# LOA_Damballah.net
KiCad netlist of a schematic drawn in EAGLE
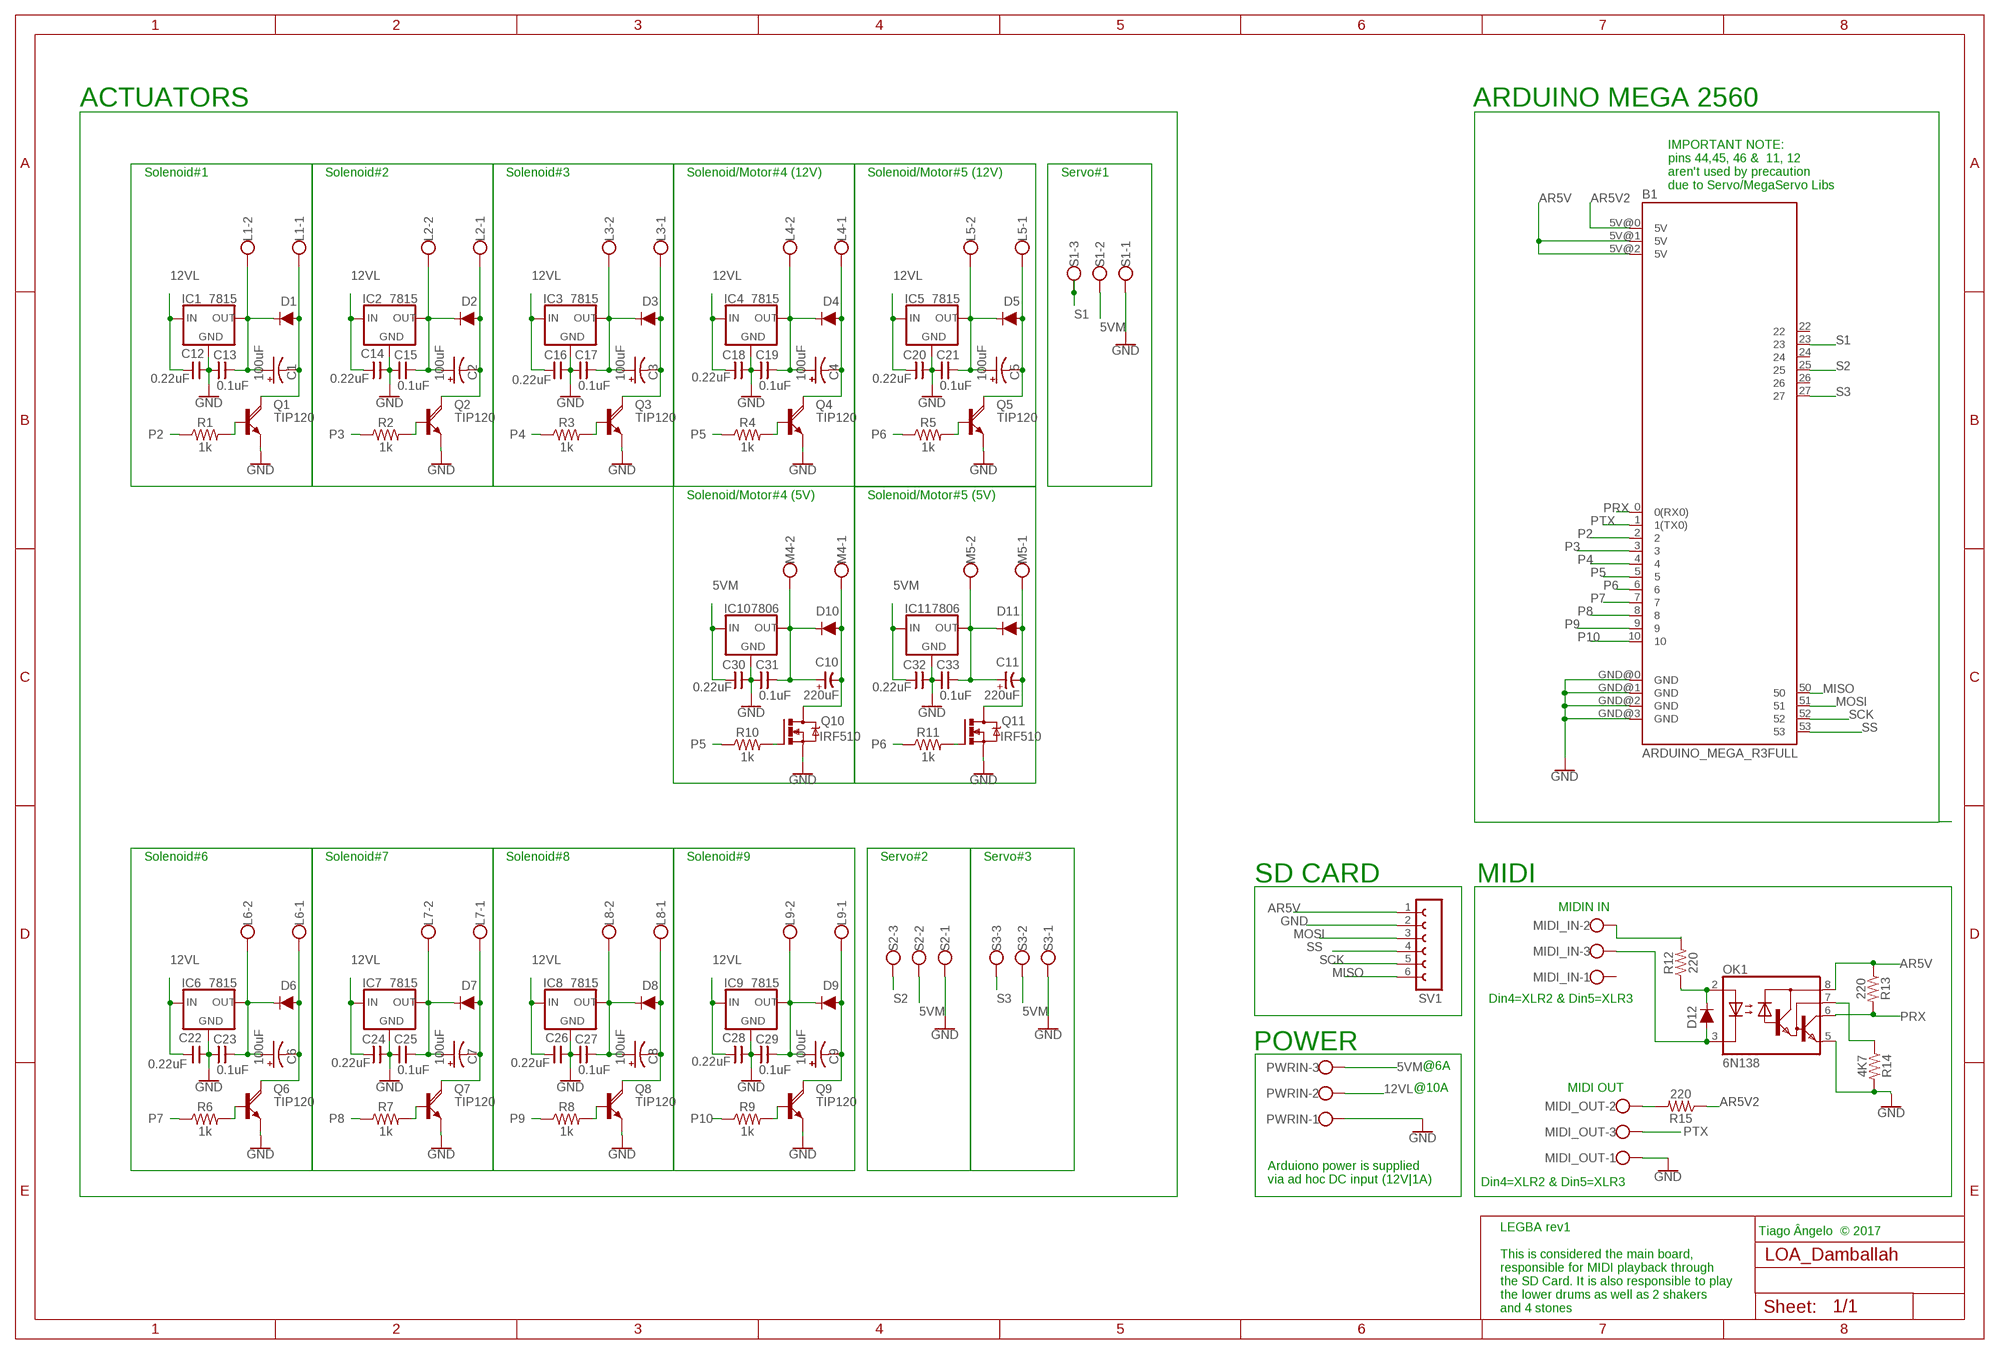
[diagram p0: schematic, sheet 1]

(export (version "E")
  (design (tool "Eeschema 10.0.6"))
  (components
    (comp (ref "B1")
      (value "ARDUINO_MEGA_R3FULL")
      (footprint "eagle-import:ARDUINO_MEGA")
      (libsource (lib "eagle-import") (part "ARDUINO_MEGA_R3FULL"))
    )
    (comp (ref "C1")
      (value "100uF")
      (footprint "eagle-import:E3,5-8")
      (libsource (lib "eagle-import") (part "CPOL-USE3.5-8"))
    )
    (comp (ref "C2")
      (value "100uF")
      (footprint "eagle-import:E3,5-8")
      (libsource (lib "eagle-import") (part "CPOL-USE3.5-8"))
    )
    (comp (ref "C3")
      (value "100uF")
      (footprint "eagle-import:E3,5-8")
      (libsource (lib "eagle-import") (part "CPOL-USE3.5-8"))
    )
    (comp (ref "C4")
      (value "100uF")
      (footprint "eagle-import:E3,5-8")
      (libsource (lib "eagle-import") (part "CPOL-USE3.5-8"))
    )
    (comp (ref "C5")
      (value "100uF")
      (footprint "eagle-import:E3,5-8")
      (libsource (lib "eagle-import") (part "CPOL-USE3.5-8"))
    )
    (comp (ref "C6")
      (value "100uF")
      (footprint "eagle-import:E3,5-8")
      (libsource (lib "eagle-import") (part "CPOL-USE3.5-8"))
    )
    (comp (ref "C7")
      (value "100uF")
      (footprint "eagle-import:E3,5-8")
      (libsource (lib "eagle-import") (part "CPOL-USE3.5-8"))
    )
    (comp (ref "C8")
      (value "100uF")
      (footprint "eagle-import:E3,5-8")
      (libsource (lib "eagle-import") (part "CPOL-USE3.5-8"))
    )
    (comp (ref "C9")
      (value "100uF")
      (footprint "eagle-import:E3,5-8")
      (libsource (lib "eagle-import") (part "CPOL-USE3.5-8"))
    )
    (comp (ref "C10")
      (value "220uF")
      (footprint "eagle-import:E-035X080")
      (libsource (lib "eagle-import") (part "CP-E-035X080"))
    )
    (comp (ref "C11")
      (value "220uF")
      (footprint "eagle-import:E-035X080")
      (libsource (lib "eagle-import") (part "CP-E-035X080"))
    )
    (comp (ref "C12")
      (value "0.22uF")
      (footprint "eagle-import:C025-050X025")
      (libsource (lib "eagle-import") (part "CNP-C025-050X025"))
    )
    (comp (ref "C13")
      (value "0.1uF")
      (footprint "eagle-import:C025-050X025")
      (libsource (lib "eagle-import") (part "CNP-C025-050X025"))
    )
    (comp (ref "C14")
      (value "0.22uF")
      (footprint "eagle-import:C025-050X025")
      (libsource (lib "eagle-import") (part "CNP-C025-050X025"))
    )
    (comp (ref "C15")
      (value "0.1uF")
      (footprint "eagle-import:C025-050X025")
      (libsource (lib "eagle-import") (part "CNP-C025-050X025"))
    )
    (comp (ref "C16")
      (value "0.22uF")
      (footprint "eagle-import:C025-050X025")
      (libsource (lib "eagle-import") (part "CNP-C025-050X025"))
    )
    (comp (ref "C17")
      (value "0.1uF")
      (footprint "eagle-import:C025-050X025")
      (libsource (lib "eagle-import") (part "CNP-C025-050X025"))
    )
    (comp (ref "C18")
      (value "0.22uF")
      (footprint "eagle-import:C025-050X025")
      (libsource (lib "eagle-import") (part "CNP-C025-050X025"))
    )
    (comp (ref "C19")
      (value "0.1uF")
      (footprint "eagle-import:C025-050X025")
      (libsource (lib "eagle-import") (part "CNP-C025-050X025"))
    )
    (comp (ref "C20")
      (value "0.22uF")
      (footprint "eagle-import:C025-050X025")
      (libsource (lib "eagle-import") (part "CNP-C025-050X025"))
    )
    (comp (ref "C21")
      (value "0.1uF")
      (footprint "eagle-import:C025-050X025")
      (libsource (lib "eagle-import") (part "CNP-C025-050X025"))
    )
    (comp (ref "C22")
      (value "0.22uF")
      (footprint "eagle-import:C025-050X025")
      (libsource (lib "eagle-import") (part "CNP-C025-050X025"))
    )
    (comp (ref "C23")
      (value "0.1uF")
      (footprint "eagle-import:C025-050X025")
      (libsource (lib "eagle-import") (part "CNP-C025-050X025"))
    )
    (comp (ref "C24")
      (value "0.22uF")
      (footprint "eagle-import:C025-050X025")
      (libsource (lib "eagle-import") (part "CNP-C025-050X025"))
    )
    (comp (ref "C25")
      (value "0.1uF")
      (footprint "eagle-import:C025-050X025")
      (libsource (lib "eagle-import") (part "CNP-C025-050X025"))
    )
    (comp (ref "C26")
      (value "0.22uF")
      (footprint "eagle-import:C025-050X025")
      (libsource (lib "eagle-import") (part "CNP-C025-050X025"))
    )
    (comp (ref "C27")
      (value "0.1uF")
      (footprint "eagle-import:C025-050X025")
      (libsource (lib "eagle-import") (part "CNP-C025-050X025"))
    )
    (comp (ref "C28")
      (value "0.22uF")
      (footprint "eagle-import:C025-050X025")
      (libsource (lib "eagle-import") (part "CNP-C025-050X025"))
    )
    (comp (ref "C29")
      (value "0.1uF")
      (footprint "eagle-import:C025-050X025")
      (libsource (lib "eagle-import") (part "CNP-C025-050X025"))
    )
    (comp (ref "C30")
      (value "0.22uF")
      (footprint "eagle-import:C025-050X025")
      (libsource (lib "eagle-import") (part "CNP-C025-050X025"))
    )
    (comp (ref "C31")
      (value "0.1uF")
      (footprint "eagle-import:C025-050X025")
      (libsource (lib "eagle-import") (part "CNP-C025-050X025"))
    )
    (comp (ref "C32")
      (value "0.22uF")
      (footprint "eagle-import:C025-050X025")
      (libsource (lib "eagle-import") (part "CNP-C025-050X025"))
    )
    (comp (ref "C33")
      (value "0.1uF")
      (footprint "eagle-import:C025-050X025")
      (libsource (lib "eagle-import") (part "CNP-C025-050X025"))
    )
    (comp (ref "D1")
      (value "1A/50V/1.1V")
      (footprint "eagle-import:DIODE-1N4001-KIT")
      (libsource (lib "eagle-import") (part "DIODE-KIT2"))
    )
    (comp (ref "D2")
      (value "1A/50V/1.1V")
      (footprint "eagle-import:DIODE-1N4001-KIT")
      (libsource (lib "eagle-import") (part "DIODE-KIT2"))
    )
    (comp (ref "D3")
      (value "1A/50V/1.1V")
      (footprint "eagle-import:DIODE-1N4001-KIT")
      (libsource (lib "eagle-import") (part "DIODE-KIT2"))
    )
    (comp (ref "D4")
      (value "1A/50V/1.1V")
      (footprint "eagle-import:DIODE-1N4001-KIT")
      (libsource (lib "eagle-import") (part "DIODE-KIT2"))
    )
    (comp (ref "D5")
      (value "1A/50V/1.1V")
      (footprint "eagle-import:DIODE-1N4001-KIT")
      (libsource (lib "eagle-import") (part "DIODE-KIT2"))
    )
    (comp (ref "D6")
      (value "1A/50V/1.1V")
      (footprint "eagle-import:DIODE-1N4001-KIT")
      (libsource (lib "eagle-import") (part "DIODE-KIT2"))
    )
    (comp (ref "D7")
      (value "1A/50V/1.1V")
      (footprint "eagle-import:DIODE-1N4001-KIT")
      (libsource (lib "eagle-import") (part "DIODE-KIT2"))
    )
    (comp (ref "D8")
      (value "1A/50V/1.1V")
      (footprint "eagle-import:DIODE-1N4001-KIT")
      (libsource (lib "eagle-import") (part "DIODE-KIT2"))
    )
    (comp (ref "D9")
      (value "1A/50V/1.1V")
      (footprint "eagle-import:DIODE-1N4001-KIT")
      (libsource (lib "eagle-import") (part "DIODE-KIT2"))
    )
    (comp (ref "D10")
      (value "1A/50V/1.1V")
      (footprint "eagle-import:DIODE-1N4001-KIT")
      (libsource (lib "eagle-import") (part "DIODE-KIT2"))
    )
    (comp (ref "D11")
      (value "1A/50V/1.1V")
      (footprint "eagle-import:DIODE-1N4001-KIT")
      (libsource (lib "eagle-import") (part "DIODE-KIT2"))
    )
    (comp (ref "D12")
      (value "200mA/100V/1V")
      (footprint "eagle-import:DIODE-1N4148")
      (libsource (lib "eagle-import") (part "DIODE-1N4148"))
    )
    (comp (ref "IC1")
      (value "7815")
      (footprint "eagle-import:78XXS")
      (libsource (lib "eagle-import") (part "78XXS"))
    )
    (comp (ref "IC2")
      (value "7815")
      (footprint "eagle-import:78XXS")
      (libsource (lib "eagle-import") (part "78XXS"))
    )
    (comp (ref "IC3")
      (value "7815")
      (footprint "eagle-import:78XXS")
      (libsource (lib "eagle-import") (part "78XXS"))
    )
    (comp (ref "IC4")
      (value "7815")
      (footprint "eagle-import:78XXS")
      (libsource (lib "eagle-import") (part "78XXS"))
    )
    (comp (ref "IC5")
      (value "7815")
      (footprint "eagle-import:78XXS")
      (libsource (lib "eagle-import") (part "78XXS"))
    )
    (comp (ref "IC6")
      (value "7815")
      (footprint "eagle-import:78XXS")
      (libsource (lib "eagle-import") (part "78XXS"))
    )
    (comp (ref "IC7")
      (value "7815")
      (footprint "eagle-import:78XXS")
      (libsource (lib "eagle-import") (part "78XXS"))
    )
    (comp (ref "IC8")
      (value "7815")
      (footprint "eagle-import:78XXS")
      (libsource (lib "eagle-import") (part "78XXS"))
    )
    (comp (ref "IC9")
      (value "7815")
      (footprint "eagle-import:78XXS")
      (libsource (lib "eagle-import") (part "78XXS"))
    )
    (comp (ref "IC10")
      (value "7806")
      (footprint "eagle-import:78XXS")
      (libsource (lib "eagle-import") (part "78XXS"))
    )
    (comp (ref "IC11")
      (value "7806")
      (footprint "eagle-import:78XXS")
      (libsource (lib "eagle-import") (part "78XXS"))
    )
    (comp (ref "L1")
      (value "W237-102")
      (footprint "eagle-import:W237-102")
      (fields (field (name "MPN") "237-102"))
      (libsource (lib "eagle-import") (part "W237-102"))
    )
    (comp (ref "L2")
      (value "W237-102")
      (footprint "eagle-import:W237-102")
      (fields (field (name "MPN") "237-102"))
      (libsource (lib "eagle-import") (part "W237-102"))
    )
    (comp (ref "L3")
      (value "W237-102")
      (footprint "eagle-import:W237-102")
      (fields (field (name "MPN") "237-102"))
      (libsource (lib "eagle-import") (part "W237-102"))
    )
    (comp (ref "L4")
      (value "W237-102")
      (footprint "eagle-import:W237-102")
      (fields (field (name "MPN") "237-102"))
      (libsource (lib "eagle-import") (part "W237-102"))
    )
    (comp (ref "L5")
      (value "W237-102")
      (footprint "eagle-import:W237-102")
      (fields (field (name "MPN") "237-102"))
      (libsource (lib "eagle-import") (part "W237-102"))
    )
    (comp (ref "L6")
      (value "W237-102")
      (footprint "eagle-import:W237-102")
      (fields (field (name "MPN") "237-102"))
      (libsource (lib "eagle-import") (part "W237-102"))
    )
    (comp (ref "L7")
      (value "W237-102")
      (footprint "eagle-import:W237-102")
      (fields (field (name "MPN") "237-102"))
      (libsource (lib "eagle-import") (part "W237-102"))
    )
    (comp (ref "L8")
      (value "W237-102")
      (footprint "eagle-import:W237-102")
      (fields (field (name "MPN") "237-102"))
      (libsource (lib "eagle-import") (part "W237-102"))
    )
    (comp (ref "L9")
      (value "W237-102")
      (footprint "eagle-import:W237-102")
      (fields (field (name "MPN") "237-102"))
      (libsource (lib "eagle-import") (part "W237-102"))
    )
    (comp (ref "M4")
      (value "W237-102")
      (footprint "eagle-import:W237-102")
      (fields (field (name "MPN") "237-102"))
      (libsource (lib "eagle-import") (part "W237-102"))
    )
    (comp (ref "M5")
      (value "W237-102")
      (footprint "eagle-import:W237-102")
      (fields (field (name "MPN") "237-102"))
      (libsource (lib "eagle-import") (part "W237-102"))
    )
    (comp (ref "MIDI_IN")
      (value "W237-103")
      (footprint "eagle-import:W237-103")
      (fields (field (name "MPN") "237-103"))
      (libsource (lib "eagle-import") (part "W237-103"))
    )
    (comp (ref "MIDI_OUT")
      (value "W237-103")
      (footprint "eagle-import:W237-103")
      (fields (field (name "MPN") "237-103"))
      (libsource (lib "eagle-import") (part "W237-103"))
    )
    (comp (ref "OK1")
      (value "6N138")
      (footprint "eagle-import:DIL08")
      (fields (field (name "MF") "VISHAY/TELEFUNKEN"))
      (libsource (lib "eagle-import") (part "6N138"))
    )
    (comp (ref "PWRIN")
      (value "W237-103")
      (footprint "eagle-import:W237-103")
      (fields (field (name "MPN") "237-103"))
      (libsource (lib "eagle-import") (part "W237-103"))
    )
    (comp (ref "Q1")
      (value "TIP120")
      (footprint "eagle-import:ROCKETFARM_TO220AV")
      (libsource (lib "eagle-import") (part "ROCKETFARM_TIP120V"))
    )
    (comp (ref "Q2")
      (value "TIP120")
      (footprint "eagle-import:ROCKETFARM_TO220AV")
      (libsource (lib "eagle-import") (part "ROCKETFARM_TIP120V"))
    )
    (comp (ref "Q3")
      (value "TIP120")
      (footprint "eagle-import:ROCKETFARM_TO220AV")
      (libsource (lib "eagle-import") (part "ROCKETFARM_TIP120V"))
    )
    (comp (ref "Q4")
      (value "TIP120")
      (footprint "eagle-import:ROCKETFARM_TO220AV")
      (libsource (lib "eagle-import") (part "ROCKETFARM_TIP120V"))
    )
    (comp (ref "Q5")
      (value "TIP120")
      (footprint "eagle-import:ROCKETFARM_TO220AV")
      (libsource (lib "eagle-import") (part "ROCKETFARM_TIP120V"))
    )
    (comp (ref "Q6")
      (value "TIP120")
      (footprint "eagle-import:ROCKETFARM_TO220AV")
      (libsource (lib "eagle-import") (part "ROCKETFARM_TIP120V"))
    )
    (comp (ref "Q7")
      (value "TIP120")
      (footprint "eagle-import:ROCKETFARM_TO220AV")
      (libsource (lib "eagle-import") (part "ROCKETFARM_TIP120V"))
    )
    (comp (ref "Q8")
      (value "TIP120")
      (footprint "eagle-import:ROCKETFARM_TO220AV")
      (libsource (lib "eagle-import") (part "ROCKETFARM_TIP120V"))
    )
    (comp (ref "Q9")
      (value "TIP120")
      (footprint "eagle-import:ROCKETFARM_TO220AV")
      (libsource (lib "eagle-import") (part "ROCKETFARM_TIP120V"))
    )
    (comp (ref "Q10")
      (value "IRF510")
      (footprint "eagle-import:TO220BV")
      (libsource (lib "eagle-import") (part "IRF520"))
    )
    (comp (ref "Q11")
      (value "IRF510")
      (footprint "eagle-import:TO220BV")
      (libsource (lib "eagle-import") (part "IRF520"))
    )
    (comp (ref "R1")
      (value "1k")
      (footprint "eagle-import:AXIAL-0.1")
      (libsource (lib "eagle-import") (part "1KOHM-VERT-1/4W-1%"))
    )
    (comp (ref "R2")
      (value "1k")
      (footprint "eagle-import:AXIAL-0.1")
      (libsource (lib "eagle-import") (part "1KOHM-VERT-1/4W-1%"))
    )
    (comp (ref "R3")
      (value "1k")
      (footprint "eagle-import:AXIAL-0.1")
      (libsource (lib "eagle-import") (part "1KOHM-VERT-1/4W-1%"))
    )
    (comp (ref "R4")
      (value "1k")
      (footprint "eagle-import:AXIAL-0.1")
      (libsource (lib "eagle-import") (part "1KOHM-VERT-1/4W-1%"))
    )
    (comp (ref "R5")
      (value "1k")
      (footprint "eagle-import:AXIAL-0.1")
      (libsource (lib "eagle-import") (part "1KOHM-VERT-1/4W-1%"))
    )
    (comp (ref "R6")
      (value "1k")
      (footprint "eagle-import:AXIAL-0.1")
      (libsource (lib "eagle-import") (part "1KOHM-VERT-1/4W-1%"))
    )
    (comp (ref "R7")
      (value "1k")
      (footprint "eagle-import:AXIAL-0.1")
      (libsource (lib "eagle-import") (part "1KOHM-VERT-1/4W-1%"))
    )
    (comp (ref "R8")
      (value "1k")
      (footprint "eagle-import:AXIAL-0.1")
      (libsource (lib "eagle-import") (part "1KOHM-VERT-1/4W-1%"))
    )
    (comp (ref "R9")
      (value "1k")
      (footprint "eagle-import:AXIAL-0.1")
      (libsource (lib "eagle-import") (part "1KOHM-VERT-1/4W-1%"))
    )
    (comp (ref "R10")
      (value "1k")
      (footprint "eagle-import:AXIAL-0.1")
      (libsource (lib "eagle-import") (part "1KOHM-VERT-1/4W-1%"))
    )
    (comp (ref "R11")
      (value "1k")
      (footprint "eagle-import:AXIAL-0.1")
      (libsource (lib "eagle-import") (part "1KOHM-VERT-1/4W-1%"))
    )
    (comp (ref "R12")
      (value "220")
      (footprint "eagle-import:AXIAL-0.3")
      (libsource (lib "eagle-import") (part "1KOHM-HORIZ-1/4W-5%"))
    )
    (comp (ref "R13")
      (value "220")
      (footprint "eagle-import:AXIAL-0.3")
      (libsource (lib "eagle-import") (part "1KOHM-HORIZ-1/4W-5%"))
    )
    (comp (ref "R14")
      (value "4K7")
      (footprint "eagle-import:AXIAL-0.3")
      (libsource (lib "eagle-import") (part "1KOHM-HORIZ-1/4W-5%"))
    )
    (comp (ref "R15")
      (value "220")
      (footprint "eagle-import:AXIAL-0.3")
      (libsource (lib "eagle-import") (part "1KOHM-HORIZ-1/4W-5%"))
    )
    (comp (ref "S1")
      (value "W237-103")
      (footprint "eagle-import:W237-103")
      (fields (field (name "MPN") "237-103"))
      (libsource (lib "eagle-import") (part "W237-103"))
    )
    (comp (ref "S2")
      (value "W237-103")
      (footprint "eagle-import:W237-103")
      (fields (field (name "MPN") "237-103"))
      (libsource (lib "eagle-import") (part "W237-103"))
    )
    (comp (ref "S3")
      (value "W237-103")
      (footprint "eagle-import:W237-103")
      (fields (field (name "MPN") "237-103"))
      (libsource (lib "eagle-import") (part "W237-103"))
    )
    (comp (ref "SV1")
      (value "FE06W")
      (footprint "eagle-import:FE06W")
      (libsource (lib "eagle-import") (part "FE06W"))
    )
  )
  (nets
    (net (code "1") (name "/5VM") (class "Default")
      (node (ref "C30") (pin "1") (pinfunction "1_1") (pintype "passive"))
      (node (ref "C32") (pin "1") (pinfunction "1_1") (pintype "passive"))
      (node (ref "IC10") (pin "IN") (pinfunction "IN_IN") (pintype "input"))
      (node (ref "IC11") (pin "IN") (pinfunction "IN_IN") (pintype "input"))
      (node (ref "PWRIN") (pin "3") (pinfunction "KL_3") (pintype "passive"))
      (node (ref "S1") (pin "2") (pinfunction "KL_2") (pintype "passive"))
      (node (ref "S2") (pin "2") (pinfunction "KL_2") (pintype "passive"))
      (node (ref "S3") (pin "2") (pinfunction "KL_2") (pintype "passive"))
    )
    (net (code "2") (name "/12VL") (class "Default")
      (node (ref "C12") (pin "1") (pinfunction "1_1") (pintype "passive"))
      (node (ref "C14") (pin "1") (pinfunction "1_1") (pintype "passive"))
      (node (ref "C16") (pin "1") (pinfunction "1_1") (pintype "passive"))
      (node (ref "C18") (pin "1") (pinfunction "1_1") (pintype "passive"))
      (node (ref "C20") (pin "1") (pinfunction "1_1") (pintype "passive"))
      (node (ref "C22") (pin "1") (pinfunction "1_1") (pintype "passive"))
      (node (ref "C24") (pin "1") (pinfunction "1_1") (pintype "passive"))
      (node (ref "C26") (pin "1") (pinfunction "1_1") (pintype "passive"))
      (node (ref "C28") (pin "1") (pinfunction "1_1") (pintype "passive"))
      (node (ref "IC1") (pin "IN") (pinfunction "IN_IN") (pintype "input"))
      (node (ref "IC2") (pin "IN") (pinfunction "IN_IN") (pintype "input"))
      (node (ref "IC3") (pin "IN") (pinfunction "IN_IN") (pintype "input"))
      (node (ref "IC4") (pin "IN") (pinfunction "IN_IN") (pintype "input"))
      (node (ref "IC5") (pin "IN") (pinfunction "IN_IN") (pintype "input"))
      (node (ref "IC6") (pin "IN") (pinfunction "IN_IN") (pintype "input"))
      (node (ref "IC7") (pin "IN") (pinfunction "IN_IN") (pintype "input"))
      (node (ref "IC8") (pin "IN") (pinfunction "IN_IN") (pintype "input"))
      (node (ref "IC9") (pin "IN") (pinfunction "IN_IN") (pintype "input"))
      (node (ref "PWRIN") (pin "2") (pinfunction "KL_2") (pintype "passive"))
    )
    (net (code "3") (name "/AR5V") (class "Default")
      (node (ref "B1") (pin "5V@1") (pinfunction "5V_5V@1") (pintype "bidirectional"))
      (node (ref "B1") (pin "5V@2") (pinfunction "5V_5V@2") (pintype "bidirectional"))
      (node (ref "OK1") (pin "8") (pinfunction "VCC_8") (pintype "passive"))
      (node (ref "R13") (pin "P$1") (pinfunction "1_P$1") (pintype "passive"))
      (node (ref "SV1") (pin "1") (pinfunction "1_1") (pintype "passive"))
    )
    (net (code "4") (name "/AR5V2") (class "Default")
      (node (ref "B1") (pin "5V@0") (pinfunction "5V_5V@0") (pintype "bidirectional"))
      (node (ref "R15") (pin "P$1") (pinfunction "1_P$1") (pintype "passive"))
    )
    (net (code "5") (name "/MISO") (class "Default")
      (node (ref "B1") (pin "50") (pinfunction "50_50") (pintype "bidirectional"))
      (node (ref "SV1") (pin "6") (pinfunction "6_6") (pintype "passive"))
    )
    (net (code "6") (name "/MOSI") (class "Default")
      (node (ref "B1") (pin "51") (pinfunction "51_51") (pintype "bidirectional"))
      (node (ref "SV1") (pin "3") (pinfunction "3_3") (pintype "passive"))
    )
    (net (code "7") (name "/P2") (class "Default")
      (node (ref "B1") (pin "2") (pinfunction "2_2") (pintype "bidirectional"))
      (node (ref "R1") (pin "P$1") (pinfunction "1_P$1") (pintype "passive"))
    )
    (net (code "8") (name "/P3") (class "Default")
      (node (ref "B1") (pin "3") (pinfunction "3_3") (pintype "bidirectional"))
      (node (ref "R2") (pin "P$1") (pinfunction "1_P$1") (pintype "passive"))
    )
    (net (code "9") (name "/P4") (class "Default")
      (node (ref "B1") (pin "4") (pinfunction "4_4") (pintype "bidirectional"))
      (node (ref "R3") (pin "P$1") (pinfunction "1_P$1") (pintype "passive"))
    )
    (net (code "10") (name "/P5") (class "Default")
      (node (ref "B1") (pin "5") (pinfunction "5_5") (pintype "bidirectional"))
      (node (ref "R10") (pin "P$1") (pinfunction "1_P$1") (pintype "passive"))
      (node (ref "R4") (pin "P$1") (pinfunction "1_P$1") (pintype "passive"))
    )
    (net (code "11") (name "/P6") (class "Default")
      (node (ref "B1") (pin "6") (pinfunction "6_6") (pintype "bidirectional"))
      (node (ref "R11") (pin "P$1") (pinfunction "1_P$1") (pintype "passive"))
      (node (ref "R5") (pin "P$1") (pinfunction "1_P$1") (pintype "passive"))
    )
    (net (code "12") (name "/P7") (class "Default")
      (node (ref "B1") (pin "7") (pinfunction "7_7") (pintype "bidirectional"))
      (node (ref "R6") (pin "P$1") (pinfunction "1_P$1") (pintype "passive"))
    )
    (net (code "13") (name "/P8") (class "Default")
      (node (ref "B1") (pin "8") (pinfunction "8_8") (pintype "bidirectional"))
      (node (ref "R7") (pin "P$1") (pinfunction "1_P$1") (pintype "passive"))
    )
    (net (code "14") (name "/P9") (class "Default")
      (node (ref "B1") (pin "9") (pinfunction "9_9") (pintype "bidirectional"))
      (node (ref "R8") (pin "P$1") (pinfunction "1_P$1") (pintype "passive"))
    )
    (net (code "15") (name "/P10") (class "Default")
      (node (ref "B1") (pin "10") (pinfunction "10_10") (pintype "bidirectional"))
      (node (ref "R9") (pin "P$1") (pinfunction "1_P$1") (pintype "passive"))
    )
    (net (code "16") (name "/PRX") (class "Default")
      (node (ref "B1") (pin "0") (pinfunction "0(RX0)_0") (pintype "bidirectional"))
      (node (ref "OK1") (pin "6") (pinfunction "VO_6") (pintype "passive"))
      (node (ref "R13") (pin "P$2") (pinfunction "2_P$2") (pintype "passive"))
    )
    (net (code "17") (name "/PTX") (class "Default")
      (node (ref "B1") (pin "1") (pinfunction "1(TX0)_1") (pintype "bidirectional"))
      (node (ref "MIDI_OUT") (pin "3") (pinfunction "KL_3") (pintype "passive"))
    )
    (net (code "18") (name "/S1") (class "Default")
      (node (ref "B1") (pin "23") (pinfunction "23_23") (pintype "bidirectional"))
      (node (ref "S1") (pin "3") (pinfunction "KL_3") (pintype "passive"))
    )
    (net (code "19") (name "/S2") (class "Default")
      (node (ref "B1") (pin "25") (pinfunction "25_25") (pintype "bidirectional"))
      (node (ref "S2") (pin "3") (pinfunction "KL_3") (pintype "passive"))
    )
    (net (code "20") (name "/S3") (class "Default")
      (node (ref "B1") (pin "27") (pinfunction "27_27") (pintype "bidirectional"))
      (node (ref "S3") (pin "3") (pinfunction "KL_3") (pintype "passive"))
    )
    (net (code "21") (name "/SCK") (class "Default")
      (node (ref "B1") (pin "52") (pinfunction "52_52") (pintype "bidirectional"))
      (node (ref "SV1") (pin "5") (pinfunction "5_5") (pintype "passive"))
    )
    (net (code "22") (name "/SS") (class "Default")
      (node (ref "B1") (pin "53") (pinfunction "53_53") (pintype "bidirectional"))
      (node (ref "SV1") (pin "4") (pinfunction "4_4") (pintype "passive"))
    )
    (net (code "23") (name "GND") (class "Default")
      (node (ref "B1") (pin "GND@0") (pinfunction "GND_GND@0") (pintype "bidirectional"))
      (node (ref "B1") (pin "GND@1") (pinfunction "GND_GND@1") (pintype "bidirectional"))
      (node (ref "B1") (pin "GND@2") (pinfunction "GND_GND@2") (pintype "bidirectional"))
      (node (ref "B1") (pin "GND@3") (pinfunction "GND_GND@3") (pintype "bidirectional"))
      (node (ref "C12") (pin "2") (pinfunction "2_2") (pintype "passive"))
      (node (ref "C13") (pin "1") (pinfunction "1_1") (pintype "passive"))
      (node (ref "C14") (pin "2") (pinfunction "2_2") (pintype "passive"))
      (node (ref "C15") (pin "1") (pinfunction "1_1") (pintype "passive"))
      (node (ref "C16") (pin "2") (pinfunction "2_2") (pintype "passive"))
      (node (ref "C17") (pin "1") (pinfunction "1_1") (pintype "passive"))
      (node (ref "C18") (pin "2") (pinfunction "2_2") (pintype "passive"))
      (node (ref "C19") (pin "1") (pinfunction "1_1") (pintype "passive"))
      (node (ref "C20") (pin "2") (pinfunction "2_2") (pintype "passive"))
      (node (ref "C21") (pin "1") (pinfunction "1_1") (pintype "passive"))
      (node (ref "C22") (pin "2") (pinfunction "2_2") (pintype "passive"))
      (node (ref "C23") (pin "1") (pinfunction "1_1") (pintype "passive"))
      (node (ref "C24") (pin "2") (pinfunction "2_2") (pintype "passive"))
      (node (ref "C25") (pin "1") (pinfunction "1_1") (pintype "passive"))
      (node (ref "C26") (pin "2") (pinfunction "2_2") (pintype "passive"))
      (node (ref "C27") (pin "1") (pinfunction "1_1") (pintype "passive"))
      (node (ref "C28") (pin "2") (pinfunction "2_2") (pintype "passive"))
      (node (ref "C29") (pin "1") (pinfunction "1_1") (pintype "passive"))
      (node (ref "C30") (pin "2") (pinfunction "2_2") (pintype "passive"))
      (node (ref "C31") (pin "1") (pinfunction "1_1") (pintype "passive"))
      (node (ref "C32") (pin "2") (pinfunction "2_2") (pintype "passive"))
      (node (ref "C33") (pin "1") (pinfunction "1_1") (pintype "passive"))
      (node (ref "IC1") (pin "GND") (pinfunction "GND_GND") (pintype "input"))
      (node (ref "IC10") (pin "GND") (pinfunction "GND_GND") (pintype "input"))
      (node (ref "IC11") (pin "GND") (pinfunction "GND_GND") (pintype "input"))
      (node (ref "IC2") (pin "GND") (pinfunction "GND_GND") (pintype "input"))
      (node (ref "IC3") (pin "GND") (pinfunction "GND_GND") (pintype "input"))
      (node (ref "IC4") (pin "GND") (pinfunction "GND_GND") (pintype "input"))
      (node (ref "IC5") (pin "GND") (pinfunction "GND_GND") (pintype "input"))
      (node (ref "IC6") (pin "GND") (pinfunction "GND_GND") (pintype "input"))
      (node (ref "IC7") (pin "GND") (pinfunction "GND_GND") (pintype "input"))
      (node (ref "IC8") (pin "GND") (pinfunction "GND_GND") (pintype "input"))
      (node (ref "IC9") (pin "GND") (pinfunction "GND_GND") (pintype "input"))
      (node (ref "MIDI_OUT") (pin "1") (pinfunction "KL_1") (pintype "passive"))
      (node (ref "OK1") (pin "5") (pinfunction "GND_5") (pintype "passive"))
      (node (ref "PWRIN") (pin "1") (pinfunction "KL_1") (pintype "passive"))
      (node (ref "Q1") (pin "E") (pinfunction "E_E") (pintype "passive"))
      (node (ref "Q10") (pin "S") (pinfunction "S_S") (pintype "passive"))
      (node (ref "Q11") (pin "S") (pinfunction "S_S") (pintype "passive"))
      (node (ref "Q2") (pin "E") (pinfunction "E_E") (pintype "passive"))
      (node (ref "Q3") (pin "E") (pinfunction "E_E") (pintype "passive"))
      (node (ref "Q4") (pin "E") (pinfunction "E_E") (pintype "passive"))
      (node (ref "Q5") (pin "E") (pinfunction "E_E") (pintype "passive"))
      (node (ref "Q6") (pin "E") (pinfunction "E_E") (pintype "passive"))
      (node (ref "Q7") (pin "E") (pinfunction "E_E") (pintype "passive"))
      (node (ref "Q8") (pin "E") (pinfunction "E_E") (pintype "passive"))
      (node (ref "Q9") (pin "E") (pinfunction "E_E") (pintype "passive"))
      (node (ref "R14") (pin "P$2") (pinfunction "2_P$2") (pintype "passive"))
      (node (ref "S1") (pin "1") (pinfunction "KL_1") (pintype "passive"))
      (node (ref "S2") (pin "1") (pinfunction "KL_1") (pintype "passive"))
      (node (ref "S3") (pin "1") (pinfunction "KL_1") (pintype "passive"))
      (node (ref "SV1") (pin "2") (pinfunction "2_2") (pintype "passive"))
    )
    (net (code "24") (name "Net-(L1A-KL)") (class "Default")
      (node (ref "C1") (pin "-") (pinfunction "-_-") (pintype "passive"))
      (node (ref "D1") (pin "A") (pinfunction "A_A") (pintype "passive"))
      (node (ref "L1") (pin "1") (pinfunction "KL_1") (pintype "passive"))
      (node (ref "Q1") (pin "C") (pinfunction "C_C") (pintype "passive"))
    )
    (net (code "25") (name "Net-(L1B-KL)") (class "Default")
      (node (ref "C1") (pin "+") (pinfunction "+_+") (pintype "passive"))
      (node (ref "C13") (pin "2") (pinfunction "2_2") (pintype "passive"))
      (node (ref "D1") (pin "C") (pinfunction "C_C") (pintype "passive"))
      (node (ref "IC1") (pin "OUT") (pinfunction "OUT_OUT") (pintype "passive"))
      (node (ref "L1") (pin "2") (pinfunction "KL_2") (pintype "passive"))
    )
    (net (code "26") (name "Net-(L2A-KL)") (class "Default")
      (node (ref "C2") (pin "-") (pinfunction "-_-") (pintype "passive"))
      (node (ref "D2") (pin "A") (pinfunction "A_A") (pintype "passive"))
      (node (ref "L2") (pin "1") (pinfunction "KL_1") (pintype "passive"))
      (node (ref "Q2") (pin "C") (pinfunction "C_C") (pintype "passive"))
    )
    (net (code "27") (name "Net-(L2B-KL)") (class "Default")
      (node (ref "C15") (pin "2") (pinfunction "2_2") (pintype "passive"))
      (node (ref "C2") (pin "+") (pinfunction "+_+") (pintype "passive"))
      (node (ref "D2") (pin "C") (pinfunction "C_C") (pintype "passive"))
      (node (ref "IC2") (pin "OUT") (pinfunction "OUT_OUT") (pintype "passive"))
      (node (ref "L2") (pin "2") (pinfunction "KL_2") (pintype "passive"))
    )
    (net (code "28") (name "Net-(L3A-KL)") (class "Default")
      (node (ref "C3") (pin "-") (pinfunction "-_-") (pintype "passive"))
      (node (ref "D3") (pin "A") (pinfunction "A_A") (pintype "passive"))
      (node (ref "L3") (pin "1") (pinfunction "KL_1") (pintype "passive"))
      (node (ref "Q3") (pin "C") (pinfunction "C_C") (pintype "passive"))
    )
    (net (code "29") (name "Net-(L3B-KL)") (class "Default")
      (node (ref "C17") (pin "2") (pinfunction "2_2") (pintype "passive"))
      (node (ref "C3") (pin "+") (pinfunction "+_+") (pintype "passive"))
      (node (ref "D3") (pin "C") (pinfunction "C_C") (pintype "passive"))
      (node (ref "IC3") (pin "OUT") (pinfunction "OUT_OUT") (pintype "passive"))
      (node (ref "L3") (pin "2") (pinfunction "KL_2") (pintype "passive"))
    )
    (net (code "30") (name "Net-(L4A-KL)") (class "Default")
      (node (ref "C4") (pin "-") (pinfunction "-_-") (pintype "passive"))
      (node (ref "D4") (pin "A") (pinfunction "A_A") (pintype "passive"))
      (node (ref "L4") (pin "1") (pinfunction "KL_1") (pintype "passive"))
      (node (ref "Q4") (pin "C") (pinfunction "C_C") (pintype "passive"))
    )
    (net (code "31") (name "Net-(L4B-KL)") (class "Default")
      (node (ref "C19") (pin "2") (pinfunction "2_2") (pintype "passive"))
      (node (ref "C4") (pin "+") (pinfunction "+_+") (pintype "passive"))
      (node (ref "D4") (pin "C") (pinfunction "C_C") (pintype "passive"))
      (node (ref "IC4") (pin "OUT") (pinfunction "OUT_OUT") (pintype "passive"))
      (node (ref "L4") (pin "2") (pinfunction "KL_2") (pintype "passive"))
    )
    (net (code "32") (name "Net-(L5A-KL)") (class "Default")
      (node (ref "C5") (pin "-") (pinfunction "-_-") (pintype "passive"))
      (node (ref "D5") (pin "A") (pinfunction "A_A") (pintype "passive"))
      (node (ref "L5") (pin "1") (pinfunction "KL_1") (pintype "passive"))
      (node (ref "Q5") (pin "C") (pinfunction "C_C") (pintype "passive"))
    )
    (net (code "33") (name "Net-(L5B-KL)") (class "Default")
      (node (ref "C21") (pin "2") (pinfunction "2_2") (pintype "passive"))
      (node (ref "C5") (pin "+") (pinfunction "+_+") (pintype "passive"))
      (node (ref "D5") (pin "C") (pinfunction "C_C") (pintype "passive"))
      (node (ref "IC5") (pin "OUT") (pinfunction "OUT_OUT") (pintype "passive"))
      (node (ref "L5") (pin "2") (pinfunction "KL_2") (pintype "passive"))
    )
    (net (code "34") (name "Net-(L6A-KL)") (class "Default")
      (node (ref "C6") (pin "-") (pinfunction "-_-") (pintype "passive"))
      (node (ref "D6") (pin "A") (pinfunction "A_A") (pintype "passive"))
      (node (ref "L6") (pin "1") (pinfunction "KL_1") (pintype "passive"))
      (node (ref "Q6") (pin "C") (pinfunction "C_C") (pintype "passive"))
    )
    (net (code "35") (name "Net-(L6B-KL)") (class "Default")
      (node (ref "C23") (pin "2") (pinfunction "2_2") (pintype "passive"))
      (node (ref "C6") (pin "+") (pinfunction "+_+") (pintype "passive"))
      (node (ref "D6") (pin "C") (pinfunction "C_C") (pintype "passive"))
      (node (ref "IC6") (pin "OUT") (pinfunction "OUT_OUT") (pintype "passive"))
      (node (ref "L6") (pin "2") (pinfunction "KL_2") (pintype "passive"))
    )
    (net (code "36") (name "Net-(L7A-KL)") (class "Default")
      (node (ref "C7") (pin "-") (pinfunction "-_-") (pintype "passive"))
      (node (ref "D7") (pin "A") (pinfunction "A_A") (pintype "passive"))
      (node (ref "L7") (pin "1") (pinfunction "KL_1") (pintype "passive"))
      (node (ref "Q7") (pin "C") (pinfunction "C_C") (pintype "passive"))
    )
    (net (code "37") (name "Net-(L7B-KL)") (class "Default")
      (node (ref "C25") (pin "2") (pinfunction "2_2") (pintype "passive"))
      (node (ref "C7") (pin "+") (pinfunction "+_+") (pintype "passive"))
      (node (ref "D7") (pin "C") (pinfunction "C_C") (pintype "passive"))
      (node (ref "IC7") (pin "OUT") (pinfunction "OUT_OUT") (pintype "passive"))
      (node (ref "L7") (pin "2") (pinfunction "KL_2") (pintype "passive"))
    )
    (net (code "38") (name "Net-(L8A-KL)") (class "Default")
      (node (ref "C8") (pin "-") (pinfunction "-_-") (pintype "passive"))
      (node (ref "D8") (pin "A") (pinfunction "A_A") (pintype "passive"))
      (node (ref "L8") (pin "1") (pinfunction "KL_1") (pintype "passive"))
      (node (ref "Q8") (pin "C") (pinfunction "C_C") (pintype "passive"))
    )
    (net (code "39") (name "Net-(L8B-KL)") (class "Default")
      (node (ref "C27") (pin "2") (pinfunction "2_2") (pintype "passive"))
      (node (ref "C8") (pin "+") (pinfunction "+_+") (pintype "passive"))
      (node (ref "D8") (pin "C") (pinfunction "C_C") (pintype "passive"))
      (node (ref "IC8") (pin "OUT") (pinfunction "OUT_OUT") (pintype "passive"))
      (node (ref "L8") (pin "2") (pinfunction "KL_2") (pintype "passive"))
    )
    (net (code "40") (name "Net-(L9A-KL)") (class "Default")
      (node (ref "C9") (pin "-") (pinfunction "-_-") (pintype "passive"))
      (node (ref "D9") (pin "A") (pinfunction "A_A") (pintype "passive"))
      (node (ref "L9") (pin "1") (pinfunction "KL_1") (pintype "passive"))
      (node (ref "Q9") (pin "C") (pinfunction "C_C") (pintype "passive"))
    )
    (net (code "41") (name "Net-(L9B-KL)") (class "Default")
      (node (ref "C29") (pin "2") (pinfunction "2_2") (pintype "passive"))
      (node (ref "C9") (pin "+") (pinfunction "+_+") (pintype "passive"))
      (node (ref "D9") (pin "C") (pinfunction "C_C") (pintype "passive"))
      (node (ref "IC9") (pin "OUT") (pinfunction "OUT_OUT") (pintype "passive"))
      (node (ref "L9") (pin "2") (pinfunction "KL_2") (pintype "passive"))
    )
    (net (code "42") (name "Net-(M4A-KL)") (class "Default")
      (node (ref "C10") (pin "-") (pinfunction "-_-") (pintype "passive"))
      (node (ref "D10") (pin "A") (pinfunction "A_A") (pintype "passive"))
      (node (ref "M4") (pin "1") (pinfunction "KL_1") (pintype "passive"))
      (node (ref "Q10") (pin "D") (pinfunction "D_D") (pintype "passive"))
    )
    (net (code "43") (name "Net-(M4B-KL)") (class "Default")
      (node (ref "C10") (pin "+") (pinfunction "+_+") (pintype "passive"))
      (node (ref "C31") (pin "2") (pinfunction "2_2") (pintype "passive"))
      (node (ref "D10") (pin "C") (pinfunction "C_C") (pintype "passive"))
      (node (ref "IC10") (pin "OUT") (pinfunction "OUT_OUT") (pintype "passive"))
      (node (ref "M4") (pin "2") (pinfunction "KL_2") (pintype "passive"))
    )
    (net (code "44") (name "Net-(M5A-KL)") (class "Default")
      (node (ref "C11") (pin "-") (pinfunction "-_-") (pintype "passive"))
      (node (ref "D11") (pin "A") (pinfunction "A_A") (pintype "passive"))
      (node (ref "M5") (pin "1") (pinfunction "KL_1") (pintype "passive"))
      (node (ref "Q11") (pin "D") (pinfunction "D_D") (pintype "passive"))
    )
    (net (code "45") (name "Net-(M5B-KL)") (class "Default")
      (node (ref "C11") (pin "+") (pinfunction "+_+") (pintype "passive"))
      (node (ref "C33") (pin "2") (pinfunction "2_2") (pintype "passive"))
      (node (ref "D11") (pin "C") (pinfunction "C_C") (pintype "passive"))
      (node (ref "IC11") (pin "OUT") (pinfunction "OUT_OUT") (pintype "passive"))
      (node (ref "M5") (pin "2") (pinfunction "KL_2") (pintype "passive"))
    )
    (net (code "46") (name "Net-(MIDI_INB-KL)") (class "Default")
      (node (ref "MIDI_IN") (pin "2") (pinfunction "KL_2") (pintype "passive"))
      (node (ref "R12") (pin "P$2") (pinfunction "2_P$2") (pintype "passive"))
    )
    (net (code "47") (name "Net-(MIDI_INC-KL)") (class "Default")
      (node (ref "D12") (pin "A") (pinfunction "A_A") (pintype "passive"))
      (node (ref "MIDI_IN") (pin "3") (pinfunction "KL_3") (pintype "passive"))
      (node (ref "OK1") (pin "3") (pinfunction "C_3") (pintype "passive"))
    )
    (net (code "48") (name "Net-(MIDI_OUTB-KL)") (class "Default")
      (node (ref "MIDI_OUT") (pin "2") (pinfunction "KL_2") (pintype "passive"))
      (node (ref "R15") (pin "P$2") (pinfunction "2_P$2") (pintype "passive"))
    )
    (net (code "49") (name "Net-(OK1-A)") (class "Default")
      (node (ref "D12") (pin "C") (pinfunction "C_C") (pintype "passive"))
      (node (ref "OK1") (pin "2") (pinfunction "A_2") (pintype "passive"))
      (node (ref "R12") (pin "P$1") (pinfunction "1_P$1") (pintype "passive"))
    )
    (net (code "50") (name "Net-(OK1-VB)") (class "Default")
      (node (ref "OK1") (pin "7") (pinfunction "VB_7") (pintype "passive"))
      (node (ref "R14") (pin "P$1") (pinfunction "1_P$1") (pintype "passive"))
    )
    (net (code "51") (name "Net-(R1-2)") (class "Default")
      (node (ref "Q1") (pin "B") (pinfunction "B_B") (pintype "passive"))
      (node (ref "R1") (pin "P$2") (pinfunction "2_P$2") (pintype "passive"))
    )
    (net (code "52") (name "Net-(R2-2)") (class "Default")
      (node (ref "Q2") (pin "B") (pinfunction "B_B") (pintype "passive"))
      (node (ref "R2") (pin "P$2") (pinfunction "2_P$2") (pintype "passive"))
    )
    (net (code "53") (name "Net-(R3-2)") (class "Default")
      (node (ref "Q3") (pin "B") (pinfunction "B_B") (pintype "passive"))
      (node (ref "R3") (pin "P$2") (pinfunction "2_P$2") (pintype "passive"))
    )
    (net (code "54") (name "Net-(R4-2)") (class "Default")
      (node (ref "Q4") (pin "B") (pinfunction "B_B") (pintype "passive"))
      (node (ref "R4") (pin "P$2") (pinfunction "2_P$2") (pintype "passive"))
    )
    (net (code "55") (name "Net-(R5-2)") (class "Default")
      (node (ref "Q5") (pin "B") (pinfunction "B_B") (pintype "passive"))
      (node (ref "R5") (pin "P$2") (pinfunction "2_P$2") (pintype "passive"))
    )
    (net (code "56") (name "Net-(R6-2)") (class "Default")
      (node (ref "Q6") (pin "B") (pinfunction "B_B") (pintype "passive"))
      (node (ref "R6") (pin "P$2") (pinfunction "2_P$2") (pintype "passive"))
    )
    (net (code "57") (name "Net-(R7-2)") (class "Default")
      (node (ref "Q7") (pin "B") (pinfunction "B_B") (pintype "passive"))
      (node (ref "R7") (pin "P$2") (pinfunction "2_P$2") (pintype "passive"))
    )
    (net (code "58") (name "Net-(R8-2)") (class "Default")
      (node (ref "Q8") (pin "B") (pinfunction "B_B") (pintype "passive"))
      (node (ref "R8") (pin "P$2") (pinfunction "2_P$2") (pintype "passive"))
    )
    (net (code "59") (name "Net-(R9-2)") (class "Default")
      (node (ref "Q9") (pin "B") (pinfunction "B_B") (pintype "passive"))
      (node (ref "R9") (pin "P$2") (pinfunction "2_P$2") (pintype "passive"))
    )
    (net (code "60") (name "Net-(R10-2)") (class "Default")
      (node (ref "Q10") (pin "G") (pinfunction "G_G") (pintype "passive"))
      (node (ref "R10") (pin "P$2") (pinfunction "2_P$2") (pintype "passive"))
    )
    (net (code "61") (name "Net-(R11-2)") (class "Default")
      (node (ref "Q11") (pin "G") (pinfunction "G_G") (pintype "passive"))
      (node (ref "R11") (pin "P$2") (pinfunction "2_P$2") (pintype "passive"))
    )
    (net (code "62") (name "unconnected-(B1-Pad22)") (class "Default")
      (node (ref "B1") (pin "22") (pinfunction "22_22") (pintype "bidirectional"))
    )
    (net (code "63") (name "unconnected-(B1-Pad24)") (class "Default")
      (node (ref "B1") (pin "24") (pinfunction "24_24") (pintype "bidirectional"))
    )
    (net (code "64") (name "unconnected-(B1-Pad26)") (class "Default")
      (node (ref "B1") (pin "26") (pinfunction "26_26") (pintype "bidirectional"))
    )
    (net (code "65") (name "unconnected-(MIDI_INA-KL-Pad1)") (class "Default")
      (node (ref "MIDI_IN") (pin "1") (pinfunction "KL_1") (pintype "passive"))
    )
  )
)
